# Qwiic_LED_Stick.net
KiCad netlist of a schematic drawn in EAGLE
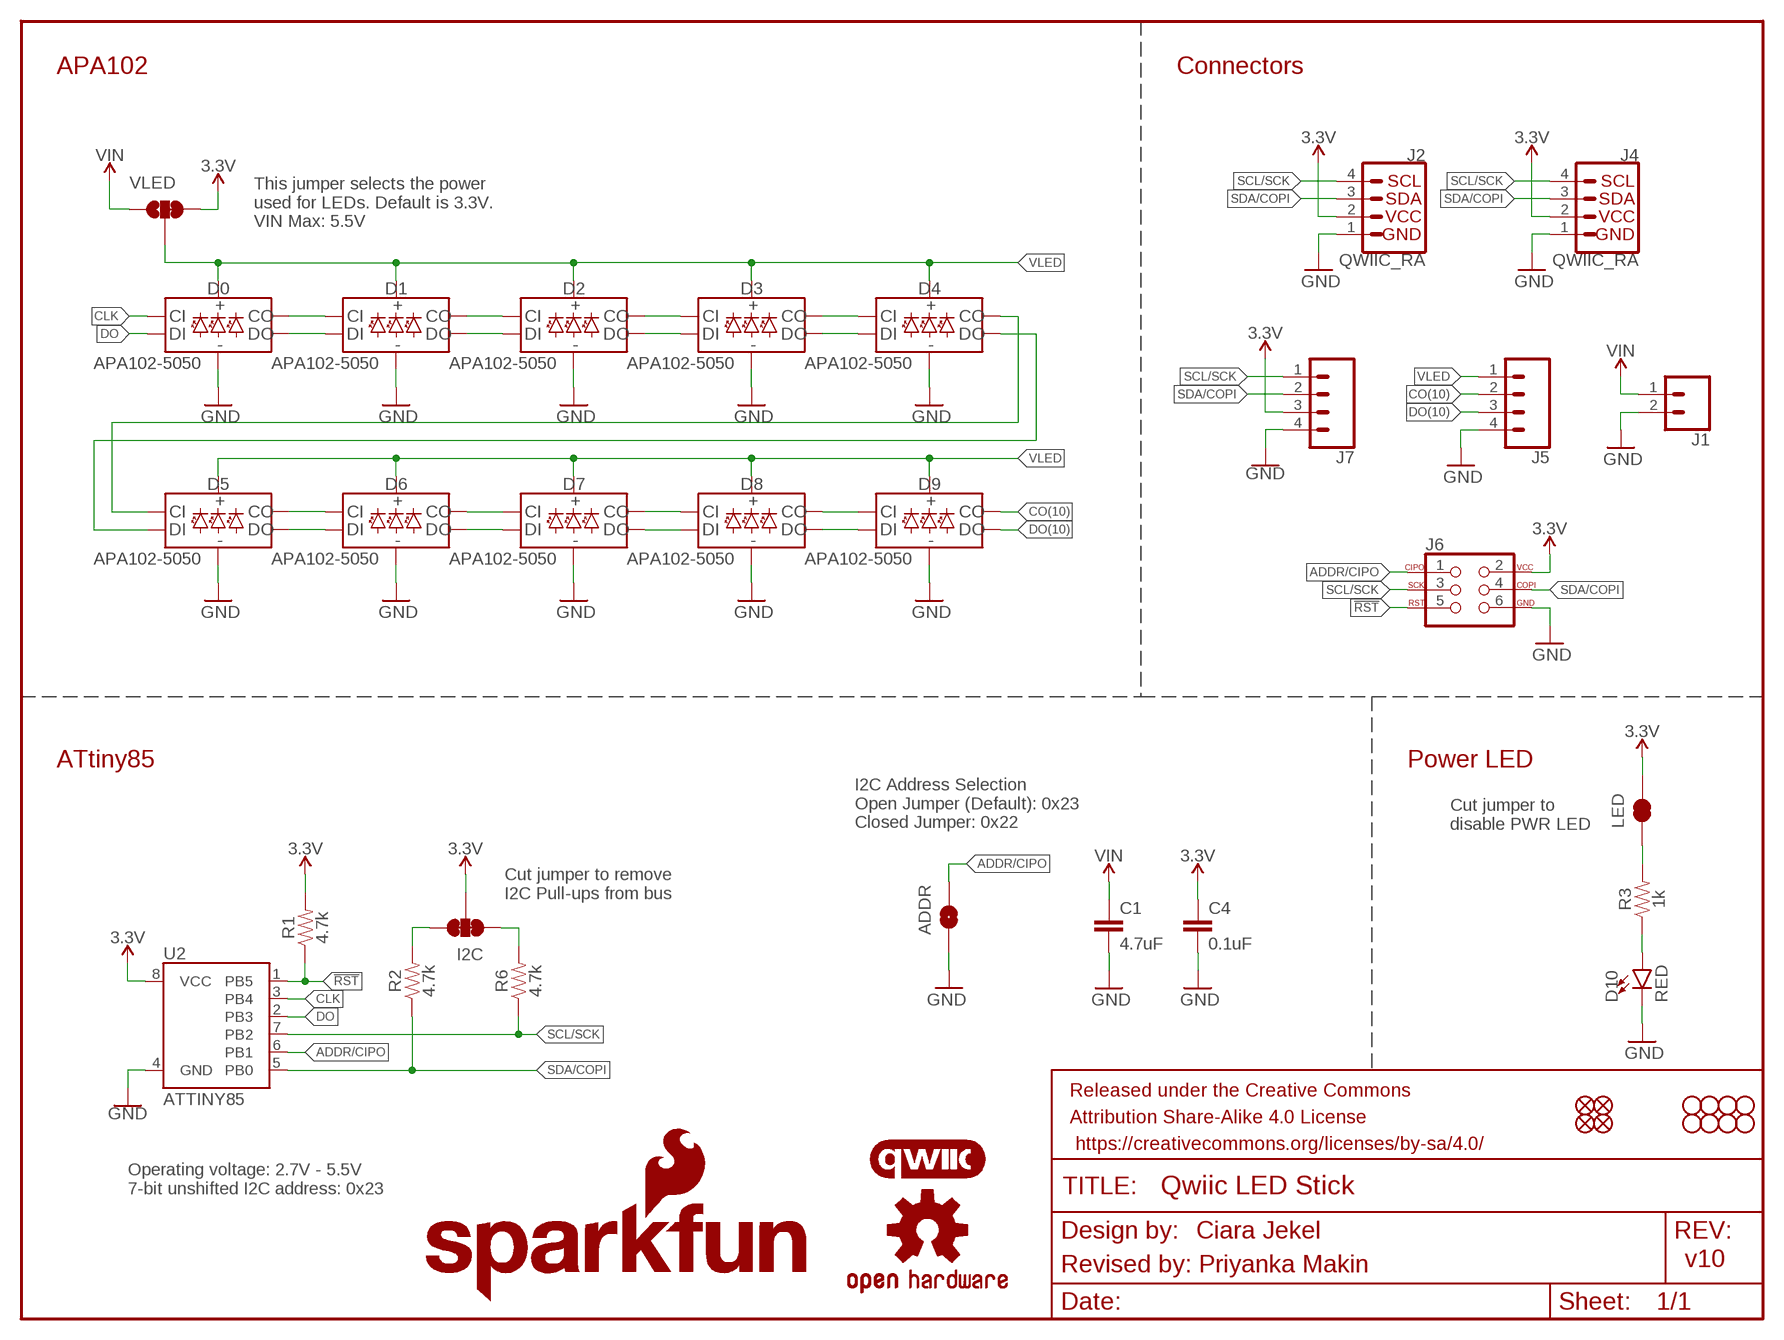
[diagram p0: schematic, sheet 1]

(export (version "E")
  (design (tool "Eeschema 10.0.6"))
  (components
    (comp (ref "ADDR")
      (value "JUMPER-SMT_2_NO_SILK")
      (footprint "eagle-import:SMT-JUMPER_2_NO_SILK")
      (libsource (lib "eagle-import") (part "JUMPER-SMT_2_NO_SILK"))
    )
    (comp (ref "C1")
      (value "4.7uF")
      (footprint "eagle-import:0603")
      (libsource (lib "eagle-import") (part "4.7UF-0603-6.3V-(10%)"))
    )
    (comp (ref "C4")
      (value "0.1uF")
      (footprint "eagle-import:0603")
      (libsource (lib "eagle-import") (part "0.1UF-0603-25V-(+80/-20%)"))
    )
    (comp (ref "D0")
      (value "APA102-5050")
      (footprint "eagle-import:APA102-5050")
      (libsource (lib "eagle-import") (part "APA102-5050"))
    )
    (comp (ref "D1")
      (value "APA102-5050")
      (footprint "eagle-import:APA102-5050")
      (libsource (lib "eagle-import") (part "APA102-5050"))
    )
    (comp (ref "D2")
      (value "APA102-5050")
      (footprint "eagle-import:APA102-5050")
      (libsource (lib "eagle-import") (part "APA102-5050"))
    )
    (comp (ref "D3")
      (value "APA102-5050")
      (footprint "eagle-import:APA102-5050")
      (libsource (lib "eagle-import") (part "APA102-5050"))
    )
    (comp (ref "D4")
      (value "APA102-5050")
      (footprint "eagle-import:APA102-5050")
      (libsource (lib "eagle-import") (part "APA102-5050"))
    )
    (comp (ref "D5")
      (value "APA102-5050")
      (footprint "eagle-import:APA102-5050")
      (libsource (lib "eagle-import") (part "APA102-5050"))
    )
    (comp (ref "D6")
      (value "APA102-5050")
      (footprint "eagle-import:APA102-5050")
      (libsource (lib "eagle-import") (part "APA102-5050"))
    )
    (comp (ref "D7")
      (value "APA102-5050")
      (footprint "eagle-import:APA102-5050")
      (libsource (lib "eagle-import") (part "APA102-5050"))
    )
    (comp (ref "D8")
      (value "APA102-5050")
      (footprint "eagle-import:APA102-5050")
      (libsource (lib "eagle-import") (part "APA102-5050"))
    )
    (comp (ref "D9")
      (value "APA102-5050")
      (footprint "eagle-import:APA102-5050")
      (libsource (lib "eagle-import") (part "APA102-5050"))
    )
    (comp (ref "D10")
      (value "RED")
      (footprint "eagle-import:LED-0603")
      (libsource (lib "eagle-import") (part "LED-RED0603"))
    )
    (comp (ref "FRAME1")
      (value "FRAME-LETTER")
      (footprint "eagle-import:CREATIVE_COMMONS")
      (libsource (lib "eagle-import") (part "FRAME-LETTER"))
    )
    (comp (ref "H1")
      (value "STAND-OFF")
      (footprint "eagle-import:STAND-OFF")
      (libsource (lib "eagle-import") (part "STAND-OFF"))
    )
    (comp (ref "H2")
      (value "STAND-OFF")
      (footprint "eagle-import:STAND-OFF")
      (libsource (lib "eagle-import") (part "STAND-OFF"))
    )
    (comp (ref "H3")
      (value "STAND-OFF")
      (footprint "eagle-import:STAND-OFF")
      (libsource (lib "eagle-import") (part "STAND-OFF"))
    )
    (comp (ref "H4")
      (value "STAND-OFF")
      (footprint "eagle-import:STAND-OFF")
      (libsource (lib "eagle-import") (part "STAND-OFF"))
    )
    (comp (ref "I2C")
      (value "JUMPER-SMT_3_2-NC_TRACE_SILK")
      (footprint "eagle-import:SMT-JUMPER_3_2-NC_TRACE_SILK")
      (libsource (lib "eagle-import") (part "JUMPER-SMT_3_2-NC_TRACE_SILK"))
    )
    (comp (ref "J1")
      (value "CONN_021X02_NO_SILK")
      (footprint "eagle-import:1X02_NO_SILK")
      (libsource (lib "eagle-import") (part "CONN_021X02_NO_SILK"))
    )
    (comp (ref "J2")
      (value "QWIIC_RA")
      (footprint "eagle-import:JST04_1MM_RA")
      (libsource (lib "eagle-import") (part "QWIIC_CONNECTORJS-1MM"))
    )
    (comp (ref "J4")
      (value "QWIIC_RA")
      (footprint "eagle-import:JST04_1MM_RA")
      (libsource (lib "eagle-import") (part "QWIIC_CONNECTORJS-1MM"))
    )
    (comp (ref "J5")
      (value "CONN_041X04_NO_SILK")
      (footprint "eagle-import:1X04_NO_SILK")
      (libsource (lib "eagle-import") (part "CONN_041X04_NO_SILK"))
    )
    (comp (ref "J6")
      (value "AVR_SPI_PROG_3X2TESTPOINTS")
      (footprint "eagle-import:2X3_TEST_POINTS")
      (libsource (lib "eagle-import") (part "AVR_SPI_PROG_3X2TESTPOINTS"))
    )
    (comp (ref "J7")
      (value "CONN_041X04_NO_SILK_NO_POP")
      (footprint "eagle-import:1X04_NO_SILK")
      (libsource (lib "eagle-import") (part "CONN_041X04_NO_SILK_NO_POP"))
    )
    (comp (ref "JP1")
      (value "FIDUCIALUFIDUCIAL")
      (footprint "eagle-import:FIDUCIAL-MICRO")
      (libsource (lib "eagle-import") (part "FIDUCIALUFIDUCIAL"))
    )
    (comp (ref "JP2")
      (value "FIDUCIALUFIDUCIAL")
      (footprint "eagle-import:FIDUCIAL-MICRO")
      (libsource (lib "eagle-import") (part "FIDUCIALUFIDUCIAL"))
    )
    (comp (ref "JP3")
      (value "STAND-OFF")
      (footprint "eagle-import:STAND-OFF")
      (libsource (lib "eagle-import") (part "STAND-OFF"))
    )
    (comp (ref "JP4")
      (value "STAND-OFF")
      (footprint "eagle-import:STAND-OFF")
      (libsource (lib "eagle-import") (part "STAND-OFF"))
    )
    (comp (ref "JP5")
      (value "FIDUCIALUFIDUCIAL")
      (footprint "eagle-import:FIDUCIAL-MICRO")
      (libsource (lib "eagle-import") (part "FIDUCIALUFIDUCIAL"))
    )
    (comp (ref "JP6")
      (value "FIDUCIALUFIDUCIAL")
      (footprint "eagle-import:FIDUCIAL-MICRO")
      (libsource (lib "eagle-import") (part "FIDUCIALUFIDUCIAL"))
    )
    (comp (ref "JP7")
      (value "STAND-OFF")
      (footprint "eagle-import:STAND-OFF")
      (libsource (lib "eagle-import") (part "STAND-OFF"))
    )
    (comp (ref "JP8")
      (value "STAND-OFF")
      (footprint "eagle-import:STAND-OFF")
      (libsource (lib "eagle-import") (part "STAND-OFF"))
    )
    (comp (ref "LED")
      (value "JUMPER-SMT_2_NC_TRACE_SILK")
      (footprint "eagle-import:SMT-JUMPER_2_NC_TRACE_SILK")
      (libsource (lib "eagle-import") (part "JUMPER-SMT_2_NC_TRACE_SILK"))
    )
    (comp (ref "LOGO1")
      (value "OSHW-LOGOMINI")
      (footprint "eagle-import:OSHW-LOGO-MINI")
      (libsource (lib "eagle-import") (part "OSHW-LOGOMINI"))
    )
    (comp (ref "LOGO2")
      (value "SFE_LOGO_NAME.2_INCH")
      (footprint "eagle-import:SFE_LOGO_NAME_.2")
      (libsource (lib "eagle-import") (part "SFE_LOGO_NAME.2_INCH"))
    )
    (comp (ref "LOGO3")
      (value "QWIIC_LOGO_5MM")
      (footprint "eagle-import:QWIIC_5MM")
      (libsource (lib "eagle-import") (part "QWIIC_LOGO_5MM"))
    )
    (comp (ref "LOGO4")
      (value "SFE_LOGO_FLAME.2_INCH")
      (footprint "eagle-import:SFE_LOGO_FLAME_.2")
      (libsource (lib "eagle-import") (part "SFE_LOGO_FLAME.2_INCH"))
    )
    (comp (ref "LOGO5")
      (value "SFE_LOGO_NAME.2_INCH")
      (footprint "eagle-import:SFE_LOGO_NAME_.2")
      (libsource (lib "eagle-import") (part "SFE_LOGO_NAME.2_INCH"))
    )
    (comp (ref "R1")
      (value "4.7k")
      (footprint "eagle-import:0603")
      (libsource (lib "eagle-import") (part "4.7KOHM-0603-1/10W-1%"))
    )
    (comp (ref "R2")
      (value "4.7k")
      (footprint "eagle-import:0603")
      (libsource (lib "eagle-import") (part "4.7KOHM-0603-1/10W-1%"))
    )
    (comp (ref "R3")
      (value "1k")
      (footprint "eagle-import:0603")
      (libsource (lib "eagle-import") (part "1KOHM-0603-1/10W-1%"))
    )
    (comp (ref "R6")
      (value "4.7k")
      (footprint "eagle-import:0603")
      (libsource (lib "eagle-import") (part "4.7KOHM-0603-1/10W-1%"))
    )
    (comp (ref "U2")
      (value "ATTINY85")
      (footprint "eagle-import:ATTINY85")
      (libsource (lib "eagle-import") (part "ATTINY85"))
    )
    (comp (ref "VLED")
      (value "JUMPER-SMT_3_1-NC_TRACE_SILK")
      (footprint "eagle-import:SMT-JUMPER_3_1-NC_TRACE_SILK")
      (libsource (lib "eagle-import") (part "JUMPER-SMT_3_1-NC_TRACE_SILK"))
    )
  )
  (nets
    (net (code "1") (name "/~{RST}") (class "Default")
      (node (ref "J6") (pin "5") (pinfunction "5_5") (pintype "passive"))
      (node (ref "R1") (pin "1") (pinfunction "1_1") (pintype "passive"))
      (node (ref "U2") (pin "1") (pinfunction "PB5_1") (pintype "bidirectional"))
    )
    (net (code "2") (name "3.3V") (class "Default")
      (node (ref "C4") (pin "1") (pinfunction "1_1") (pintype "passive"))
      (node (ref "I2C") (pin "2") (pinfunction "2_2") (pintype "passive"))
      (node (ref "J2") (pin "2") (pinfunction "2_2") (pintype "power_in"))
      (node (ref "J4") (pin "2") (pinfunction "2_2") (pintype "power_in"))
      (node (ref "J6") (pin "2") (pinfunction "2_2") (pintype "passive"))
      (node (ref "J7") (pin "3") (pinfunction "3_3") (pintype "passive"))
      (node (ref "LED") (pin "2") (pinfunction "2_2") (pintype "passive"))
      (node (ref "R1") (pin "2") (pinfunction "2_2") (pintype "passive"))
      (node (ref "U2") (pin "8") (pinfunction "VCC_8") (pintype "bidirectional"))
      (node (ref "VLED") (pin "3") (pinfunction "3_3") (pintype "passive"))
    )
    (net (code "3") (name "ADDR{slash}CIPO") (class "Default")
      (node (ref "ADDR") (pin "2") (pinfunction "2_2") (pintype "passive"))
      (node (ref "J6") (pin "1") (pinfunction "1_1") (pintype "passive"))
      (node (ref "U2") (pin "6") (pinfunction "PB1_6") (pintype "bidirectional"))
    )
    (net (code "4") (name "CLK") (class "Default")
      (node (ref "D0") (pin "P2") (pinfunction "CI_P2") (pintype "bidirectional"))
      (node (ref "U2") (pin "3") (pinfunction "PB4_3") (pintype "bidirectional"))
    )
    (net (code "5") (name "CO(10)") (class "Default")
      (node (ref "D9") (pin "P5") (pinfunction "CO_P5") (pintype "bidirectional"))
      (node (ref "J5") (pin "2") (pinfunction "2_2") (pintype "passive"))
    )
    (net (code "6") (name "DO") (class "Default")
      (node (ref "D0") (pin "P1") (pinfunction "DI_P1") (pintype "bidirectional"))
      (node (ref "U2") (pin "2") (pinfunction "PB3_2") (pintype "bidirectional"))
    )
    (net (code "7") (name "DO(10)") (class "Default")
      (node (ref "D9") (pin "P6") (pinfunction "DO_P6") (pintype "bidirectional"))
      (node (ref "J5") (pin "3") (pinfunction "3_3") (pintype "passive"))
    )
    (net (code "8") (name "GND") (class "Default")
      (node (ref "ADDR") (pin "1") (pinfunction "1_1") (pintype "passive"))
      (node (ref "C1") (pin "2") (pinfunction "2_2") (pintype "passive"))
      (node (ref "C4") (pin "2") (pinfunction "2_2") (pintype "passive"))
      (node (ref "D0") (pin "P3") (pinfunction "GND_P3") (pintype "bidirectional"))
      (node (ref "D1") (pin "P3") (pinfunction "GND_P3") (pintype "bidirectional"))
      (node (ref "D10") (pin "C") (pinfunction "C_C") (pintype "passive"))
      (node (ref "D2") (pin "P3") (pinfunction "GND_P3") (pintype "bidirectional"))
      (node (ref "D3") (pin "P3") (pinfunction "GND_P3") (pintype "bidirectional"))
      (node (ref "D4") (pin "P3") (pinfunction "GND_P3") (pintype "bidirectional"))
      (node (ref "D5") (pin "P3") (pinfunction "GND_P3") (pintype "bidirectional"))
      (node (ref "D6") (pin "P3") (pinfunction "GND_P3") (pintype "bidirectional"))
      (node (ref "D7") (pin "P3") (pinfunction "GND_P3") (pintype "bidirectional"))
      (node (ref "D8") (pin "P3") (pinfunction "GND_P3") (pintype "bidirectional"))
      (node (ref "D9") (pin "P3") (pinfunction "GND_P3") (pintype "bidirectional"))
      (node (ref "J1") (pin "2") (pinfunction "2_2") (pintype "passive"))
      (node (ref "J2") (pin "1") (pinfunction "1_1") (pintype "power_in"))
      (node (ref "J4") (pin "1") (pinfunction "1_1") (pintype "power_in"))
      (node (ref "J5") (pin "4") (pinfunction "4_4") (pintype "passive"))
      (node (ref "J6") (pin "6") (pinfunction "6_6") (pintype "passive"))
      (node (ref "J7") (pin "4") (pinfunction "4_4") (pintype "passive"))
      (node (ref "U2") (pin "4") (pinfunction "GND_4") (pintype "bidirectional"))
    )
    (net (code "9") (name "Net-(D0-CO)") (class "Default")
      (node (ref "D0") (pin "P5") (pinfunction "CO_P5") (pintype "bidirectional"))
      (node (ref "D1") (pin "P2") (pinfunction "CI_P2") (pintype "bidirectional"))
    )
    (net (code "10") (name "Net-(D0-DO)") (class "Default")
      (node (ref "D0") (pin "P6") (pinfunction "DO_P6") (pintype "bidirectional"))
      (node (ref "D1") (pin "P1") (pinfunction "DI_P1") (pintype "bidirectional"))
    )
    (net (code "11") (name "Net-(D1-CO)") (class "Default")
      (node (ref "D1") (pin "P5") (pinfunction "CO_P5") (pintype "bidirectional"))
      (node (ref "D2") (pin "P2") (pinfunction "CI_P2") (pintype "bidirectional"))
    )
    (net (code "12") (name "Net-(D1-DO)") (class "Default")
      (node (ref "D1") (pin "P6") (pinfunction "DO_P6") (pintype "bidirectional"))
      (node (ref "D2") (pin "P1") (pinfunction "DI_P1") (pintype "bidirectional"))
    )
    (net (code "13") (name "Net-(D2-CO)") (class "Default")
      (node (ref "D2") (pin "P5") (pinfunction "CO_P5") (pintype "bidirectional"))
      (node (ref "D3") (pin "P2") (pinfunction "CI_P2") (pintype "bidirectional"))
    )
    (net (code "14") (name "Net-(D2-DO)") (class "Default")
      (node (ref "D2") (pin "P6") (pinfunction "DO_P6") (pintype "bidirectional"))
      (node (ref "D3") (pin "P1") (pinfunction "DI_P1") (pintype "bidirectional"))
    )
    (net (code "15") (name "Net-(D3-CO)") (class "Default")
      (node (ref "D3") (pin "P5") (pinfunction "CO_P5") (pintype "bidirectional"))
      (node (ref "D4") (pin "P2") (pinfunction "CI_P2") (pintype "bidirectional"))
    )
    (net (code "16") (name "Net-(D3-DO)") (class "Default")
      (node (ref "D3") (pin "P6") (pinfunction "DO_P6") (pintype "bidirectional"))
      (node (ref "D4") (pin "P1") (pinfunction "DI_P1") (pintype "bidirectional"))
    )
    (net (code "17") (name "Net-(D4-CO)") (class "Default")
      (node (ref "D4") (pin "P5") (pinfunction "CO_P5") (pintype "bidirectional"))
      (node (ref "D5") (pin "P2") (pinfunction "CI_P2") (pintype "bidirectional"))
    )
    (net (code "18") (name "Net-(D4-DO)") (class "Default")
      (node (ref "D4") (pin "P6") (pinfunction "DO_P6") (pintype "bidirectional"))
      (node (ref "D5") (pin "P1") (pinfunction "DI_P1") (pintype "bidirectional"))
    )
    (net (code "19") (name "Net-(D5-CO)") (class "Default")
      (node (ref "D5") (pin "P5") (pinfunction "CO_P5") (pintype "bidirectional"))
      (node (ref "D6") (pin "P2") (pinfunction "CI_P2") (pintype "bidirectional"))
    )
    (net (code "20") (name "Net-(D5-DO)") (class "Default")
      (node (ref "D5") (pin "P6") (pinfunction "DO_P6") (pintype "bidirectional"))
      (node (ref "D6") (pin "P1") (pinfunction "DI_P1") (pintype "bidirectional"))
    )
    (net (code "21") (name "Net-(D6-CO)") (class "Default")
      (node (ref "D6") (pin "P5") (pinfunction "CO_P5") (pintype "bidirectional"))
      (node (ref "D7") (pin "P2") (pinfunction "CI_P2") (pintype "bidirectional"))
    )
    (net (code "22") (name "Net-(D6-DO)") (class "Default")
      (node (ref "D6") (pin "P6") (pinfunction "DO_P6") (pintype "bidirectional"))
      (node (ref "D7") (pin "P1") (pinfunction "DI_P1") (pintype "bidirectional"))
    )
    (net (code "23") (name "Net-(D7-CO)") (class "Default")
      (node (ref "D7") (pin "P5") (pinfunction "CO_P5") (pintype "bidirectional"))
      (node (ref "D8") (pin "P2") (pinfunction "CI_P2") (pintype "bidirectional"))
    )
    (net (code "24") (name "Net-(D7-DO)") (class "Default")
      (node (ref "D7") (pin "P6") (pinfunction "DO_P6") (pintype "bidirectional"))
      (node (ref "D8") (pin "P1") (pinfunction "DI_P1") (pintype "bidirectional"))
    )
    (net (code "25") (name "Net-(D8-CO)") (class "Default")
      (node (ref "D8") (pin "P5") (pinfunction "CO_P5") (pintype "bidirectional"))
      (node (ref "D9") (pin "P2") (pinfunction "CI_P2") (pintype "bidirectional"))
    )
    (net (code "26") (name "Net-(D8-DO)") (class "Default")
      (node (ref "D8") (pin "P6") (pinfunction "DO_P6") (pintype "bidirectional"))
      (node (ref "D9") (pin "P1") (pinfunction "DI_P1") (pintype "bidirectional"))
    )
    (net (code "27") (name "Net-(D10-PadA)") (class "Default")
      (node (ref "D10") (pin "A") (pinfunction "A_A") (pintype "passive"))
      (node (ref "R3") (pin "1") (pinfunction "1_1") (pintype "passive"))
    )
    (net (code "28") (name "Net-(I2C-Pad1)") (class "Default")
      (node (ref "I2C") (pin "1") (pinfunction "1_1") (pintype "passive"))
      (node (ref "R6") (pin "2") (pinfunction "2_2") (pintype "passive"))
    )
    (net (code "29") (name "Net-(I2C-Pad3)") (class "Default")
      (node (ref "I2C") (pin "3") (pinfunction "3_3") (pintype "passive"))
      (node (ref "R2") (pin "2") (pinfunction "2_2") (pintype "passive"))
    )
    (net (code "30") (name "Net-(LED-Pad1)") (class "Default")
      (node (ref "LED") (pin "1") (pinfunction "1_1") (pintype "passive"))
      (node (ref "R3") (pin "2") (pinfunction "2_2") (pintype "passive"))
    )
    (net (code "31") (name "SCL{slash}SCK") (class "Default")
      (node (ref "J2") (pin "4") (pinfunction "4_4") (pintype "passive"))
      (node (ref "J4") (pin "4") (pinfunction "4_4") (pintype "passive"))
      (node (ref "J6") (pin "3") (pinfunction "3_3") (pintype "passive"))
      (node (ref "J7") (pin "1") (pinfunction "1_1") (pintype "passive"))
      (node (ref "R6") (pin "1") (pinfunction "1_1") (pintype "passive"))
      (node (ref "U2") (pin "7") (pinfunction "PB2_7") (pintype "bidirectional"))
    )
    (net (code "32") (name "SDA{slash}COPI") (class "Default")
      (node (ref "J2") (pin "3") (pinfunction "3_3") (pintype "passive"))
      (node (ref "J4") (pin "3") (pinfunction "3_3") (pintype "passive"))
      (node (ref "J6") (pin "4") (pinfunction "4_4") (pintype "passive"))
      (node (ref "J7") (pin "2") (pinfunction "2_2") (pintype "passive"))
      (node (ref "R2") (pin "1") (pinfunction "1_1") (pintype "passive"))
      (node (ref "U2") (pin "5") (pinfunction "PB0_5") (pintype "bidirectional"))
    )
    (net (code "33") (name "VIN") (class "Default")
      (node (ref "C1") (pin "1") (pinfunction "1_1") (pintype "passive"))
      (node (ref "J1") (pin "1") (pinfunction "1_1") (pintype "passive"))
      (node (ref "VLED") (pin "1") (pinfunction "1_1") (pintype "passive"))
    )
    (net (code "34") (name "VLED") (class "Default")
      (node (ref "D0") (pin "P4") (pinfunction "VCC_P4") (pintype "bidirectional"))
      (node (ref "D1") (pin "P4") (pinfunction "VCC_P4") (pintype "bidirectional"))
      (node (ref "D2") (pin "P4") (pinfunction "VCC_P4") (pintype "bidirectional"))
      (node (ref "D3") (pin "P4") (pinfunction "VCC_P4") (pintype "bidirectional"))
      (node (ref "D4") (pin "P4") (pinfunction "VCC_P4") (pintype "bidirectional"))
      (node (ref "D5") (pin "P4") (pinfunction "VCC_P4") (pintype "bidirectional"))
      (node (ref "D6") (pin "P4") (pinfunction "VCC_P4") (pintype "bidirectional"))
      (node (ref "D7") (pin "P4") (pinfunction "VCC_P4") (pintype "bidirectional"))
      (node (ref "D8") (pin "P4") (pinfunction "VCC_P4") (pintype "bidirectional"))
      (node (ref "D9") (pin "P4") (pinfunction "VCC_P4") (pintype "bidirectional"))
      (node (ref "J5") (pin "1") (pinfunction "1_1") (pintype "passive"))
      (node (ref "VLED") (pin "2") (pinfunction "2_2") (pintype "passive"))
    )
  )
)
